# can4vscp_usb_rev_c.net
KiCad netlist of a schematic drawn in EAGLE
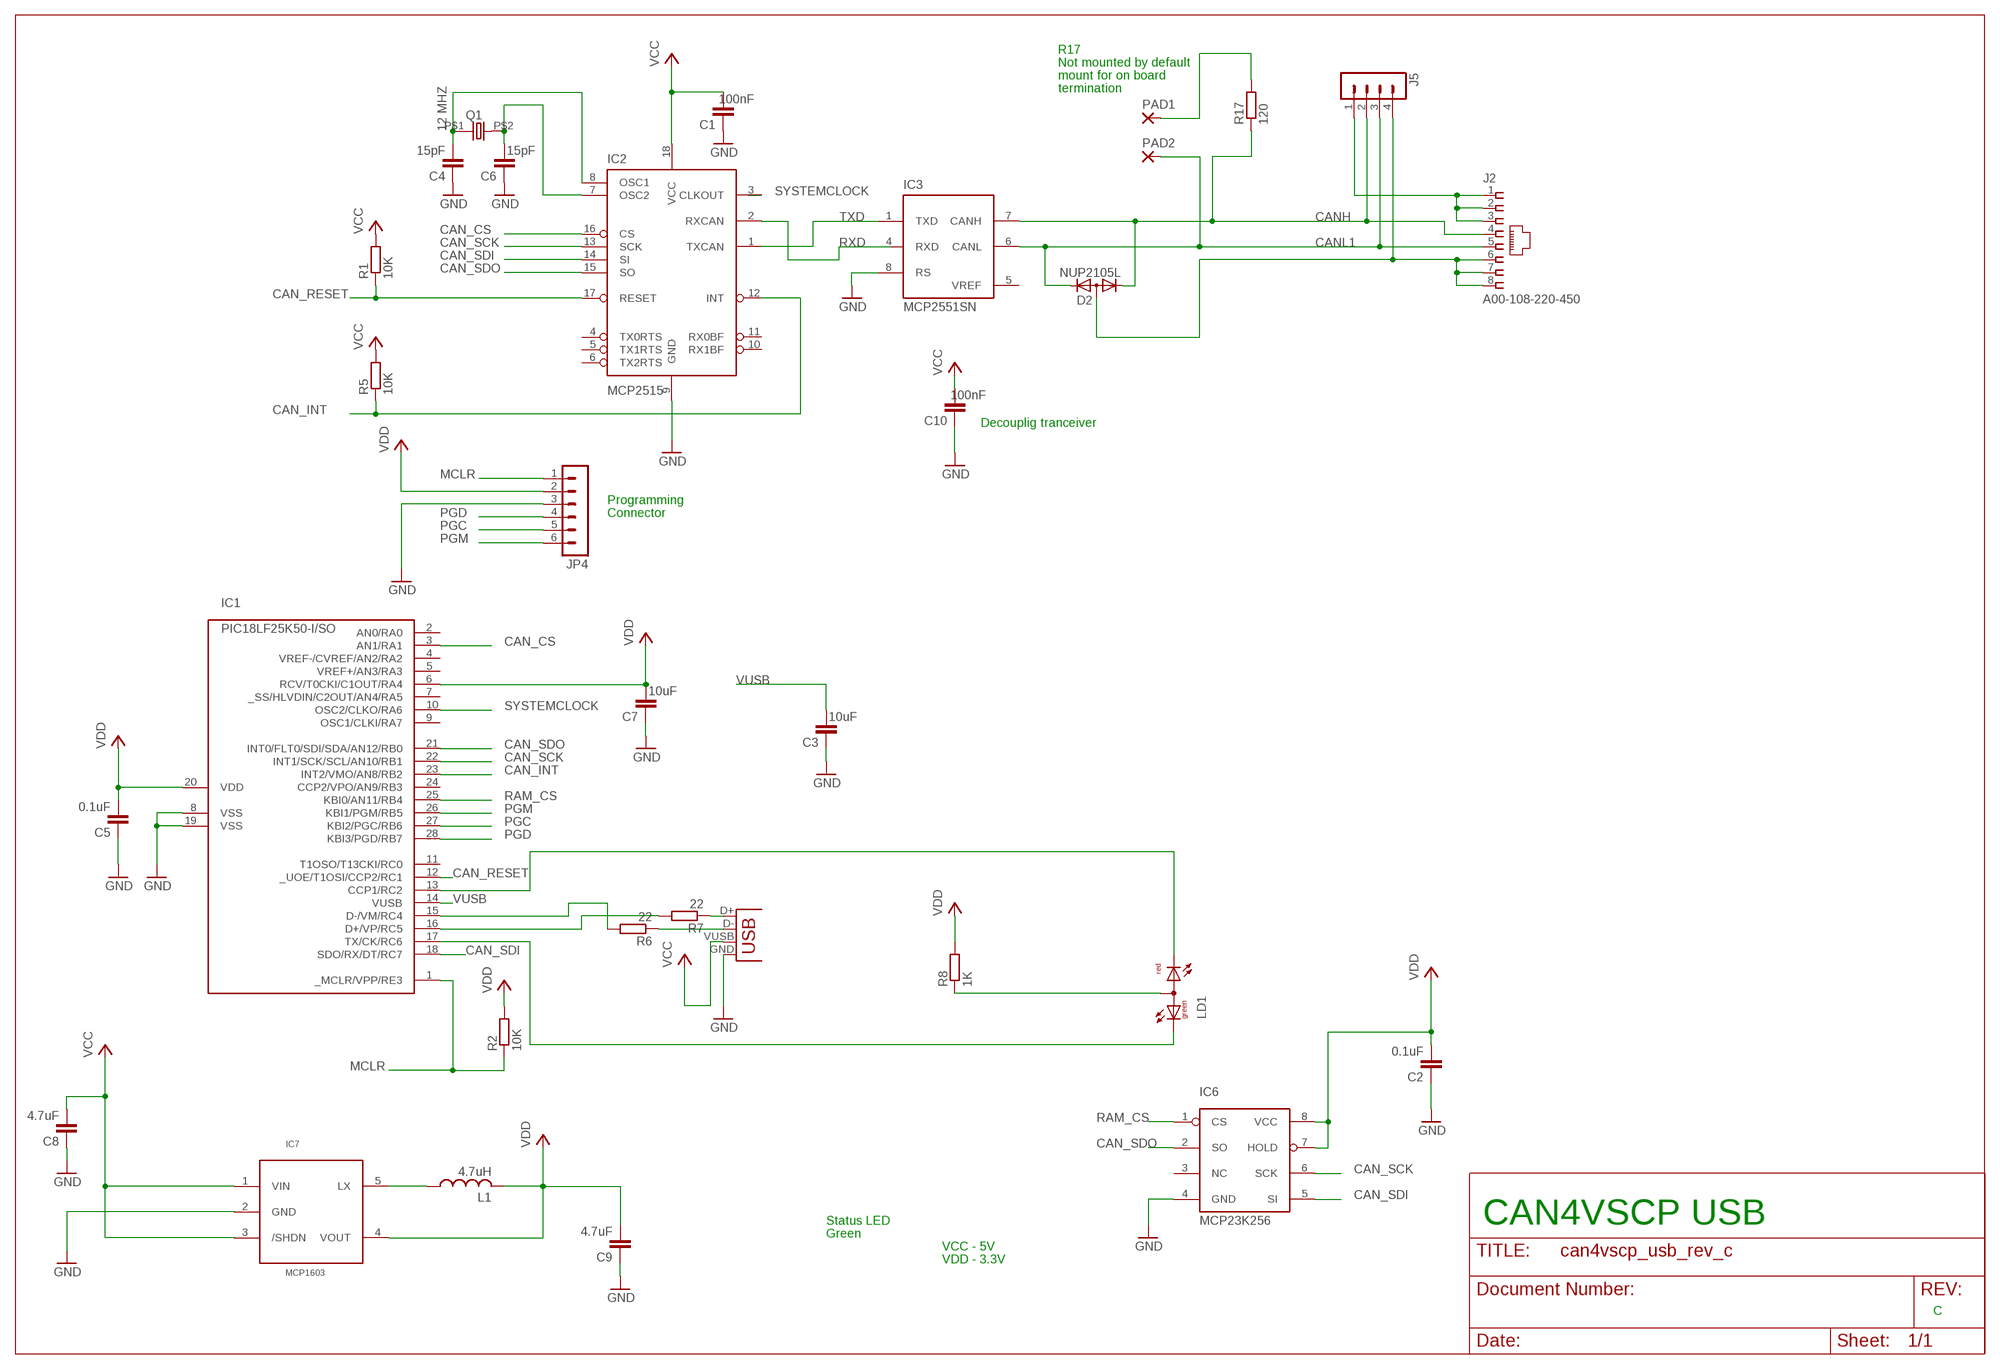
[diagram p0: schematic, sheet 1]

(export (version "E")
  (design (tool "Eeschema 10.0.6"))
  (components
    (comp (ref "C1")
      (value "100nF")
      (footprint "eagle-import:C0805")
      (libsource (lib "eagle-import") (part "C-EUC0805"))
    )
    (comp (ref "C2")
      (value "0.1uF")
      (footprint "eagle-import:C0805")
      (libsource (lib "eagle-import") (part "C-EUC0805"))
    )
    (comp (ref "C3")
      (value "10uF")
      (footprint "eagle-import:C0805")
      (libsource (lib "eagle-import") (part "C-EUC0805"))
    )
    (comp (ref "C4")
      (value "15pF")
      (footprint "eagle-import:C0805")
      (libsource (lib "eagle-import") (part "C-EUC0805"))
    )
    (comp (ref "C5")
      (value "0.1uF")
      (footprint "eagle-import:C0805")
      (libsource (lib "eagle-import") (part "C-EUC0805"))
    )
    (comp (ref "C6")
      (value "15pF")
      (footprint "eagle-import:C0805")
      (libsource (lib "eagle-import") (part "C-EUC0805"))
    )
    (comp (ref "C7")
      (value "10uF")
      (footprint "eagle-import:C0805")
      (libsource (lib "eagle-import") (part "C-EUC0805"))
    )
    (comp (ref "C8")
      (value "4.7uF")
      (footprint "eagle-import:C0805")
      (libsource (lib "eagle-import") (part "C-EUC0805"))
    )
    (comp (ref "C9")
      (value "4.7uF")
      (footprint "eagle-import:C0805")
      (libsource (lib "eagle-import") (part "C-EUC0805"))
    )
    (comp (ref "C10")
      (value "100nF")
      (footprint "eagle-import:C0805")
      (libsource (lib "eagle-import") (part "C-EUC0805"))
    )
    (comp (ref "D2")
      (value "NUP2105L")
      (footprint "eagle-import:SOT23")
      (libsource (lib "eagle-import") (part "DIODE-2CA|ACSOT23"))
    )
    (comp (ref "IC1")
      (value "PIC18LF25K50-I/SO")
      (footprint "eagle-import:SO-28W")
      (libsource (lib "eagle-import") (part "PIC182550-I/SOLF"))
    )
    (comp (ref "IC2")
      (value "MCP2515")
      (footprint "eagle-import:SO-18W")
      (libsource (lib "eagle-import") (part "MCP2515"))
    )
    (comp (ref "IC3")
      (value "MCP2551SN")
      (footprint "eagle-import:SO-08")
      (libsource (lib "eagle-import") (part "MCP2551SN"))
    )
    (comp (ref "IC6")
      (value "MCP23K256")
      (footprint "eagle-import:SO-8")
      (libsource (lib "eagle-import") (part "MCP23A256"))
    )
    (comp (ref "IC7")
      (value "MCP1603")
      (footprint "eagle-import:SOT23-5L")
      (libsource (lib "eagle-import") (part "MCP1603"))
    )
    (comp (ref "J2")
      (value "A00-108-220-450")
      (footprint "eagle-import:RJ-45")
      (libsource (lib "eagle-import") (part "A00-108-220-450"))
    )
    (comp (ref "J4")
      (value "USB-B-S")
      (footprint "eagle-import:USB-B-SMT")
      (libsource (lib "eagle-import") (part "USB-B-S"))
    )
    (comp (ref "J5")
      (value "MA04-1")
      (footprint "eagle-import:MA04-1")
      (libsource (lib "eagle-import") (part "MA04-1"))
    )
    (comp (ref "JP4")
      (value "MA06-1")
      (footprint "eagle-import:MA06-1")
      (libsource (lib "eagle-import") (part "MA06-1"))
    )
    (comp (ref "L1")
      (value "4.7uH")
      (footprint "eagle-import:L2012C")
      (libsource (lib "eagle-import") (part "L-USL2012C"))
    )
    (comp (ref "LD1")
      (value "DUOLED-RG-A")
      (footprint "eagle-import:DUOLED-A-5MM")
      (libsource (lib "eagle-import") (part "DUOLED-RG-A"))
    )
    (comp (ref "PAD1")
      (value "1,6/0,8")
      (footprint "eagle-import:1,6_0,8")
      (libsource (lib "eagle-import") (part "1,6/0,8"))
    )
    (comp (ref "PAD2")
      (value "1,6/0,8")
      (footprint "eagle-import:1,6_0,8")
      (libsource (lib "eagle-import") (part "1,6/0,8"))
    )
    (comp (ref "Q1")
      (value "12 MHZ")
      (footprint "eagle-import:9C")
      (libsource (lib "eagle-import") (part "HC-49S"))
    )
    (comp (ref "R1")
      (value "10K")
      (footprint "eagle-import:R0805")
      (libsource (lib "eagle-import") (part "R-EU_R0805"))
    )
    (comp (ref "R2")
      (value "10K")
      (footprint "eagle-import:R0805")
      (libsource (lib "eagle-import") (part "R-EU_R0805"))
    )
    (comp (ref "R5")
      (value "10K")
      (footprint "eagle-import:R0805")
      (libsource (lib "eagle-import") (part "R-EU_R0805"))
    )
    (comp (ref "R6")
      (value "22")
      (footprint "eagle-import:R0805")
      (libsource (lib "eagle-import") (part "R-EU_R0805"))
    )
    (comp (ref "R7")
      (value "22")
      (footprint "eagle-import:R0805")
      (libsource (lib "eagle-import") (part "R-EU_R0805"))
    )
    (comp (ref "R8")
      (value "1K")
      (footprint "eagle-import:R0805")
      (libsource (lib "eagle-import") (part "R-EU_R0805"))
    )
    (comp (ref "R17")
      (value "120")
      (footprint "eagle-import:R0805")
      (libsource (lib "eagle-import") (part "R-EU_R0805"))
    )
  )
  (nets
    (net (code "1") (name "/CANH") (class "Default")
      (node (ref "D2") (pin "1") (pinfunction "K1_1") (pintype "passive"))
      (node (ref "IC3") (pin "7") (pinfunction "CANH_7") (pintype "bidirectional"))
      (node (ref "J2") (pin "4") (pinfunction "4_4") (pintype "passive"))
      (node (ref "J5") (pin "2") (pinfunction "2_2") (pintype "passive"))
      (node (ref "R17") (pin "1") (pinfunction "1_1") (pintype "passive"))
    )
    (net (code "2") (name "/CANL1") (class "Default")
      (node (ref "D2") (pin "2") (pinfunction "K2_2") (pintype "passive"))
      (node (ref "IC3") (pin "6") (pinfunction "CANL_6") (pintype "bidirectional"))
      (node (ref "J2") (pin "5") (pinfunction "5_5") (pintype "passive"))
      (node (ref "J5") (pin "3") (pinfunction "3_3") (pintype "passive"))
      (node (ref "PAD2") (pin "1") (pinfunction "P_1") (pintype "passive"))
    )
    (net (code "3") (name "/CAN_CS") (class "Default")
      (node (ref "IC1") (pin "3") (pinfunction "AN1/RA1_3") (pintype "bidirectional"))
      (node (ref "IC2") (pin "16") (pinfunction "CS_16") (pintype "input"))
    )
    (net (code "4") (name "/CAN_INT") (class "Default")
      (node (ref "IC1") (pin "23") (pinfunction "INT2/VMO/AN8/RB2_23") (pintype "bidirectional"))
      (node (ref "IC2") (pin "12") (pinfunction "INT_12") (pintype "output"))
      (node (ref "R5") (pin "1") (pinfunction "1_1") (pintype "passive"))
    )
    (net (code "5") (name "/CAN_RESET") (class "Default")
      (node (ref "IC1") (pin "12") (pinfunction "_UOE/T1OSI/CCP2/RC1_12") (pintype "bidirectional"))
      (node (ref "IC2") (pin "17") (pinfunction "RESET_17") (pintype "input"))
      (node (ref "R1") (pin "1") (pinfunction "1_1") (pintype "passive"))
    )
    (net (code "6") (name "/CAN_SCK") (class "Default")
      (node (ref "IC1") (pin "22") (pinfunction "INT1/SCK/SCL/AN10/RB1_22") (pintype "bidirectional"))
      (node (ref "IC2") (pin "13") (pinfunction "SCK_13") (pintype "input"))
      (node (ref "IC6") (pin "6") (pinfunction "SCK_6") (pintype "input"))
    )
    (net (code "7") (name "/CAN_SDI") (class "Default")
      (node (ref "IC1") (pin "18") (pinfunction "SDO/RX/DT/RC7_18") (pintype "bidirectional"))
      (node (ref "IC2") (pin "14") (pinfunction "SI_14") (pintype "input"))
      (node (ref "IC6") (pin "5") (pinfunction "SI_5") (pintype "input"))
    )
    (net (code "8") (name "/CAN_SDO") (class "Default")
      (node (ref "IC1") (pin "21") (pinfunction "INT0/FLT0/SDI/SDA/AN12/RB0_21") (pintype "bidirectional"))
      (node (ref "IC2") (pin "15") (pinfunction "SO_15") (pintype "output"))
      (node (ref "IC6") (pin "2") (pinfunction "SO_2") (pintype "output"))
    )
    (net (code "9") (name "/MCLR") (class "Default")
      (node (ref "IC1") (pin "1") (pinfunction "_MCLR/VPP/RE3_1") (pintype "input"))
      (node (ref "JP4") (pin "1") (pinfunction "1_1") (pintype "passive"))
      (node (ref "R2") (pin "1") (pinfunction "1_1") (pintype "passive"))
    )
    (net (code "10") (name "/PGC") (class "Default")
      (node (ref "IC1") (pin "27") (pinfunction "KBI2/PGC/RB6_27") (pintype "bidirectional"))
      (node (ref "JP4") (pin "5") (pinfunction "5_5") (pintype "passive"))
    )
    (net (code "11") (name "/PGD") (class "Default")
      (node (ref "IC1") (pin "28") (pinfunction "KBI3/PGD/RB7_28") (pintype "bidirectional"))
      (node (ref "JP4") (pin "4") (pinfunction "4_4") (pintype "passive"))
    )
    (net (code "12") (name "/PGM") (class "Default")
      (node (ref "IC1") (pin "26") (pinfunction "KBI1/PGM/RB5_26") (pintype "bidirectional"))
      (node (ref "JP4") (pin "6") (pinfunction "6_6") (pintype "passive"))
    )
    (net (code "13") (name "/RAM_CS") (class "Default")
      (node (ref "IC1") (pin "25") (pinfunction "KBI0/AN11/RB4_25") (pintype "bidirectional"))
      (node (ref "IC6") (pin "1") (pinfunction "CS_1") (pintype "input"))
    )
    (net (code "14") (name "/RXD") (class "Default")
      (node (ref "IC2") (pin "2") (pinfunction "RXCAN_2") (pintype "input"))
    )
    (net (code "15") (name "/SYSTEMCLOCK") (class "Default")
      (node (ref "IC1") (pin "10") (pinfunction "OSC2/CLKO/RA6_10") (pintype "bidirectional"))
      (node (ref "IC2") (pin "3") (pinfunction "CLKOUT_3") (pintype "output"))
    )
    (net (code "16") (name "/TXD") (class "Default")
      (node (ref "IC2") (pin "1") (pinfunction "TXCAN_1") (pintype "output"))
      (node (ref "IC3") (pin "1") (pinfunction "TXD_1") (pintype "input"))
    )
    (net (code "17") (name "/VREF") (class "Default")
      (node (ref "IC3") (pin "5") (pinfunction "VREF_5") (pintype "power_in"))
    )
    (net (code "18") (name "/VUSB") (class "Default")
      (node (ref "C3") (pin "2") (pinfunction "2_2") (pintype "passive"))
      (node (ref "IC1") (pin "14") (pinfunction "VUSB_14") (pintype "bidirectional"))
    )
    (net (code "19") (name "GND") (class "Default")
      (node (ref "C1") (pin "1") (pinfunction "1_1") (pintype "passive"))
      (node (ref "C10") (pin "1") (pinfunction "1_1") (pintype "passive"))
      (node (ref "C2") (pin "1") (pinfunction "1_1") (pintype "passive"))
      (node (ref "C3") (pin "1") (pinfunction "1_1") (pintype "passive"))
      (node (ref "C4") (pin "1") (pinfunction "1_1") (pintype "passive"))
      (node (ref "C5") (pin "1") (pinfunction "1_1") (pintype "passive"))
      (node (ref "C6") (pin "1") (pinfunction "1_1") (pintype "passive"))
      (node (ref "C7") (pin "1") (pinfunction "1_1") (pintype "passive"))
      (node (ref "C8") (pin "1") (pinfunction "1_1") (pintype "passive"))
      (node (ref "C9") (pin "1") (pinfunction "1_1") (pintype "passive"))
      (node (ref "D2") (pin "3") (pinfunction "A_3") (pintype "passive"))
      (node (ref "IC1") (pin "19") (pinfunction "VSS_19") (pintype "power_in"))
      (node (ref "IC1") (pin "8") (pinfunction "VSS_8") (pintype "power_in"))
      (node (ref "IC2") (pin "9") (pinfunction "GND_9") (pintype "power_in"))
      (node (ref "IC3") (pin "8") (pinfunction "RS_8") (pintype "input"))
      (node (ref "IC6") (pin "4") (pinfunction "GND_4") (pintype "power_in"))
      (node (ref "IC7") (pin "2") (pinfunction "GND_2") (pintype "power_in"))
      (node (ref "J2") (pin "6") (pinfunction "6_6") (pintype "passive"))
      (node (ref "J2") (pin "7") (pinfunction "7_7") (pintype "passive"))
      (node (ref "J2") (pin "8") (pinfunction "8_8") (pintype "passive"))
      (node (ref "J4") (pin "GND") (pinfunction "GND_GND") (pintype "bidirectional"))
      (node (ref "J5") (pin "4") (pinfunction "4_4") (pintype "passive"))
      (node (ref "JP4") (pin "3") (pinfunction "3_3") (pintype "passive"))
    )
    (net (code "20") (name "Net-(IC1-CCP1{slash}RC2)") (class "Default")
      (node (ref "IC1") (pin "13") (pinfunction "CCP1/RC2_13") (pintype "bidirectional"))
      (node (ref "LD1") (pin "CR") (pinfunction "CR_CR") (pintype "passive"))
    )
    (net (code "21") (name "Net-(IC1-D+{slash}VP{slash}RC5)") (class "Default")
      (node (ref "IC1") (pin "16") (pinfunction "D+/VP/RC5_16") (pintype "bidirectional"))
      (node (ref "R7") (pin "2") (pinfunction "2_2") (pintype "passive"))
    )
    (net (code "22") (name "Net-(IC1-D-{slash}VM{slash}RC4)") (class "Default")
      (node (ref "IC1") (pin "15") (pinfunction "D-/VM/RC4_15") (pintype "bidirectional"))
      (node (ref "R6") (pin "2") (pinfunction "2_2") (pintype "passive"))
    )
    (net (code "23") (name "Net-(IC1-TX{slash}CK{slash}RC6)") (class "Default")
      (node (ref "IC1") (pin "17") (pinfunction "TX/CK/RC6_17") (pintype "bidirectional"))
      (node (ref "LD1") (pin "CX") (pinfunction "CG_CX") (pintype "passive"))
    )
    (net (code "24") (name "Net-(IC2-OSC1)") (class "Default")
      (node (ref "C4") (pin "2") (pinfunction "2_2") (pintype "passive"))
      (node (ref "IC2") (pin "8") (pinfunction "OSC1_8") (pintype "input"))
      (node (ref "Q1") (pin "P$1") (pinfunction "1_P$1") (pintype "passive"))
    )
    (net (code "25") (name "Net-(IC2-OSC2)") (class "Default")
      (node (ref "C6") (pin "2") (pinfunction "2_2") (pintype "passive"))
      (node (ref "IC2") (pin "7") (pinfunction "OSC2_7") (pintype "output"))
      (node (ref "Q1") (pin "P$2") (pinfunction "2_P$2") (pintype "passive"))
    )
    (net (code "26") (name "Net-(IC7-LX)") (class "Default")
      (node (ref "IC7") (pin "5") (pinfunction "LX_5") (pintype "bidirectional"))
      (node (ref "L1") (pin "1") (pinfunction "1_1") (pintype "passive"))
    )
    (net (code "27") (name "Net-(J2-Pad1)") (class "Default")
      (node (ref "J2") (pin "1") (pinfunction "1_1") (pintype "passive"))
      (node (ref "J2") (pin "2") (pinfunction "2_2") (pintype "passive"))
      (node (ref "J2") (pin "3") (pinfunction "3_3") (pintype "passive"))
      (node (ref "J5") (pin "1") (pinfunction "1_1") (pintype "passive"))
    )
    (net (code "28") (name "Net-(J4-PadD+)") (class "Default")
      (node (ref "J4") (pin "D+") (pinfunction "D+_D+") (pintype "bidirectional"))
      (node (ref "R7") (pin "1") (pinfunction "1_1") (pintype "passive"))
    )
    (net (code "29") (name "Net-(J4-PadD-)") (class "Default")
      (node (ref "J4") (pin "D-") (pinfunction "D-_D-") (pintype "bidirectional"))
      (node (ref "R6") (pin "1") (pinfunction "1_1") (pintype "passive"))
    )
    (net (code "30") (name "Net-(LD1-PadA)") (class "Default")
      (node (ref "LD1") (pin "A") (pinfunction "A_A") (pintype "passive"))
      (node (ref "R8") (pin "1") (pinfunction "1_1") (pintype "passive"))
    )
    (net (code "31") (name "Net-(PAD1-P)") (class "Default")
      (node (ref "PAD1") (pin "1") (pinfunction "P_1") (pintype "passive"))
      (node (ref "R17") (pin "2") (pinfunction "2_2") (pintype "passive"))
    )
    (net (code "32") (name "VCC") (class "Default")
      (node (ref "C1") (pin "2") (pinfunction "2_2") (pintype "passive"))
      (node (ref "C10") (pin "2") (pinfunction "2_2") (pintype "passive"))
      (node (ref "C8") (pin "2") (pinfunction "2_2") (pintype "passive"))
      (node (ref "IC2") (pin "18") (pinfunction "VCC_18") (pintype "power_in"))
      (node (ref "IC7") (pin "1") (pinfunction "VIN_1") (pintype "bidirectional"))
      (node (ref "IC7") (pin "3") (pinfunction "/SHDN_3") (pintype "bidirectional"))
      (node (ref "J4") (pin "VUSB") (pinfunction "VBUS_VUSB") (pintype "bidirectional"))
      (node (ref "R1") (pin "2") (pinfunction "2_2") (pintype "passive"))
      (node (ref "R5") (pin "2") (pinfunction "2_2") (pintype "passive"))
    )
    (net (code "33") (name "VDD") (class "Default")
      (node (ref "C2") (pin "2") (pinfunction "2_2") (pintype "passive"))
      (node (ref "C5") (pin "2") (pinfunction "2_2") (pintype "passive"))
      (node (ref "C7") (pin "2") (pinfunction "2_2") (pintype "passive"))
      (node (ref "C9") (pin "2") (pinfunction "2_2") (pintype "passive"))
      (node (ref "IC1") (pin "20") (pinfunction "VDD_20") (pintype "power_in"))
      (node (ref "IC1") (pin "6") (pinfunction "RCV/T0CKI/C1OUT/RA4_6") (pintype "bidirectional"))
      (node (ref "IC6") (pin "7") (pinfunction "HOLD_7") (pintype "input"))
      (node (ref "IC6") (pin "8") (pinfunction "VCC_8") (pintype "power_in"))
      (node (ref "IC7") (pin "4") (pinfunction "VOUT_4") (pintype "bidirectional"))
      (node (ref "JP4") (pin "2") (pinfunction "2_2") (pintype "passive"))
      (node (ref "L1") (pin "2") (pinfunction "2_2") (pintype "passive"))
      (node (ref "R2") (pin "2") (pinfunction "2_2") (pintype "passive"))
      (node (ref "R8") (pin "2") (pinfunction "2_2") (pintype "passive"))
    )
    (net (code "34") (name "unconnected-(IC1-AN0{slash}RA0-Pad2)") (class "Default")
      (node (ref "IC1") (pin "2") (pinfunction "AN0/RA0_2") (pintype "bidirectional"))
    )
    (net (code "35") (name "unconnected-(IC1-CCP2{slash}VPO{slash}AN9{slash}RB3-Pad24)") (class "Default")
      (node (ref "IC1") (pin "24") (pinfunction "CCP2/VPO/AN9/RB3_24") (pintype "bidirectional"))
    )
    (net (code "36") (name "unconnected-(IC1-OSC1{slash}CLKI{slash}RA7-Pad9)") (class "Default")
      (node (ref "IC1") (pin "9") (pinfunction "OSC1/CLKI/RA7_9") (pintype "bidirectional"))
    )
    (net (code "37") (name "unconnected-(IC1-T1OSO{slash}T13CKI{slash}RC0-Pad11)") (class "Default")
      (node (ref "IC1") (pin "11") (pinfunction "T1OSO/T13CKI/RC0_11") (pintype "bidirectional"))
    )
    (net (code "38") (name "unconnected-(IC1-VREF+{slash}AN3{slash}RA3-Pad5)") (class "Default")
      (node (ref "IC1") (pin "5") (pinfunction "VREF+/AN3/RA3_5") (pintype "bidirectional"))
    )
    (net (code "39") (name "unconnected-(IC1-VREF-{slash}CVREF{slash}AN2{slash}RA2-Pad4)") (class "Default")
      (node (ref "IC1") (pin "4") (pinfunction "VREF-/CVREF/AN2/RA2_4") (pintype "bidirectional"))
    )
    (net (code "40") (name "unconnected-(IC1-_SS{slash}HLVDIN{slash}C2OUT{slash}AN4{slash}RA5-Pad7)") (class "Default")
      (node (ref "IC1") (pin "7") (pinfunction "_SS/HLVDIN/C2OUT/AN4/RA5_7") (pintype "bidirectional"))
    )
    (net (code "41") (name "unconnected-(IC2-RX0BF-Pad11)") (class "Default")
      (node (ref "IC2") (pin "11") (pinfunction "RX0BF_11") (pintype "output"))
    )
    (net (code "42") (name "unconnected-(IC2-RX1BF-Pad10)") (class "Default")
      (node (ref "IC2") (pin "10") (pinfunction "RX1BF_10") (pintype "output"))
    )
    (net (code "43") (name "unconnected-(IC2-TX0RTS-Pad4)") (class "Default")
      (node (ref "IC2") (pin "4") (pinfunction "TX0RTS_4") (pintype "input"))
    )
    (net (code "44") (name "unconnected-(IC2-TX1RTS-Pad5)") (class "Default")
      (node (ref "IC2") (pin "5") (pinfunction "TX1RTS_5") (pintype "input"))
    )
    (net (code "45") (name "unconnected-(IC2-TX2RTS-Pad6)") (class "Default")
      (node (ref "IC2") (pin "6") (pinfunction "TX2RTS_6") (pintype "input"))
    )
    (net (code "46") (name "unconnected-(IC3A-RXD-Pad4)") (class "Default")
      (node (ref "IC3") (pin "4") (pinfunction "RXD_4") (pintype "output"))
    )
    (net (code "47") (name "unconnected-(IC6-NC-Pad3)") (class "Default")
      (node (ref "IC6") (pin "3") (pinfunction "NC_3") (pintype "no_connect"))
    )
  )
)
